# H-Bridge-HP.net
KiCad netlist of a schematic drawn in EAGLE
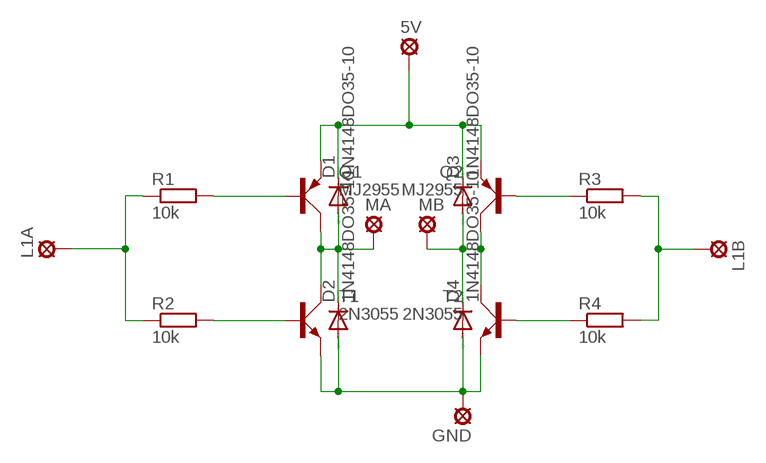
[diagram p0: schematic, sheet 1]

(export (version "E")
  (design (tool "Eeschema 10.0.6"))
  (components
    (comp (ref "5V")
      (value "LSP10")
      (footprint "eagle-import:LSP10")
      (libsource (lib "eagle-import") (part "LSP10"))
    )
    (comp (ref "D1")
      (value "1N4148DO35-10")
      (footprint "eagle-import:DO35-10")
      (libsource (lib "eagle-import") (part "1N4148DO35-10"))
    )
    (comp (ref "D2")
      (value "1N4148DO35-10")
      (footprint "eagle-import:DO35-10")
      (libsource (lib "eagle-import") (part "1N4148DO35-10"))
    )
    (comp (ref "D3")
      (value "1N4148DO35-10")
      (footprint "eagle-import:DO35-10")
      (libsource (lib "eagle-import") (part "1N4148DO35-10"))
    )
    (comp (ref "D4")
      (value "1N4148DO35-10")
      (footprint "eagle-import:DO35-10")
      (libsource (lib "eagle-import") (part "1N4148DO35-10"))
    )
    (comp (ref "GND")
      (value "LSP10")
      (footprint "eagle-import:LSP10")
      (libsource (lib "eagle-import") (part "LSP10"))
    )
    (comp (ref "L1A")
      (value "LSP10")
      (footprint "eagle-import:LSP10")
      (libsource (lib "eagle-import") (part "LSP10"))
    )
    (comp (ref "L1B")
      (value "LSP10")
      (footprint "eagle-import:LSP10")
      (libsource (lib "eagle-import") (part "LSP10"))
    )
    (comp (ref "MA")
      (value "LSP10")
      (footprint "eagle-import:LSP10")
      (libsource (lib "eagle-import") (part "LSP10"))
    )
    (comp (ref "MB")
      (value "LSP10")
      (footprint "eagle-import:LSP10")
      (libsource (lib "eagle-import") (part "LSP10"))
    )
    (comp (ref "Q1")
      (value "MJ2955")
      (footprint "eagle-import:TO3A")
      (libsource (lib "eagle-import") (part "MJ2955"))
    )
    (comp (ref "Q2")
      (value "MJ2955")
      (footprint "eagle-import:TO3A")
      (libsource (lib "eagle-import") (part "MJ2955"))
    )
    (comp (ref "R1")
      (value "10k")
      (footprint "eagle-import:0309_12")
      (libsource (lib "eagle-import") (part "R-EU_0309/12"))
    )
    (comp (ref "R2")
      (value "10k")
      (footprint "eagle-import:0309_12")
      (libsource (lib "eagle-import") (part "R-EU_0309/12"))
    )
    (comp (ref "R3")
      (value "10k")
      (footprint "eagle-import:0309_12")
      (libsource (lib "eagle-import") (part "R-EU_0309/12"))
    )
    (comp (ref "R4")
      (value "10k")
      (footprint "eagle-import:0309_12")
      (libsource (lib "eagle-import") (part "R-EU_0309/12"))
    )
    (comp (ref "T1")
      (value "2N3055")
      (footprint "eagle-import:TO3A")
      (libsource (lib "eagle-import") (part "2N3055"))
    )
    (comp (ref "T2")
      (value "2N3055")
      (footprint "eagle-import:TO3A")
      (libsource (lib "eagle-import") (part "2N3055"))
    )
  )
  (nets
    (net (code "1") (name "Net-(5V-PadMP)") (class "Default")
      (node (ref "5V") (pin "MP") (pinfunction "MP_MP") (pintype "passive"))
      (node (ref "D1") (pin "C") (pinfunction "C_C") (pintype "passive"))
      (node (ref "D3") (pin "C") (pinfunction "C_C") (pintype "passive"))
      (node (ref "Q1") (pin "E") (pinfunction "E_E") (pintype "passive"))
      (node (ref "Q2") (pin "E") (pinfunction "E_E") (pintype "passive"))
    )
    (net (code "2") (name "Net-(D1-PadA)") (class "Default")
      (node (ref "D1") (pin "A") (pinfunction "A_A") (pintype "passive"))
      (node (ref "D2") (pin "C") (pinfunction "C_C") (pintype "passive"))
      (node (ref "MA") (pin "MP") (pinfunction "MP_MP") (pintype "passive"))
      (node (ref "Q1") (pin "C") (pinfunction "C_C") (pintype "passive"))
      (node (ref "Q1") (pin "C1") (pinfunction "C_C1") (pintype "passive"))
      (node (ref "T1") (pin "C") (pinfunction "C_C") (pintype "passive"))
      (node (ref "T1") (pin "C1") (pinfunction "C_C1") (pintype "passive"))
    )
    (net (code "3") (name "Net-(D2-PadA)") (class "Default")
      (node (ref "D2") (pin "A") (pinfunction "A_A") (pintype "passive"))
      (node (ref "D4") (pin "A") (pinfunction "A_A") (pintype "passive"))
      (node (ref "GND") (pin "MP") (pinfunction "MP_MP") (pintype "passive"))
      (node (ref "T1") (pin "E") (pinfunction "E_E") (pintype "passive"))
      (node (ref "T2") (pin "E") (pinfunction "E_E") (pintype "passive"))
    )
    (net (code "4") (name "Net-(D3-PadA)") (class "Default")
      (node (ref "D3") (pin "A") (pinfunction "A_A") (pintype "passive"))
      (node (ref "D4") (pin "C") (pinfunction "C_C") (pintype "passive"))
      (node (ref "MB") (pin "MP") (pinfunction "MP_MP") (pintype "passive"))
      (node (ref "Q2") (pin "C") (pinfunction "C_C") (pintype "passive"))
      (node (ref "Q2") (pin "C1") (pinfunction "C_C1") (pintype "passive"))
      (node (ref "T2") (pin "C") (pinfunction "C_C") (pintype "passive"))
      (node (ref "T2") (pin "C1") (pinfunction "C_C1") (pintype "passive"))
    )
    (net (code "5") (name "Net-(L1A-PadMP)") (class "Default")
      (node (ref "L1A") (pin "MP") (pinfunction "MP_MP") (pintype "passive"))
      (node (ref "R1") (pin "1") (pinfunction "1_1") (pintype "passive"))
      (node (ref "R2") (pin "1") (pinfunction "1_1") (pintype "passive"))
    )
    (net (code "6") (name "Net-(L1B-PadMP)") (class "Default")
      (node (ref "L1B") (pin "MP") (pinfunction "MP_MP") (pintype "passive"))
      (node (ref "R3") (pin "2") (pinfunction "2_2") (pintype "passive"))
      (node (ref "R4") (pin "2") (pinfunction "2_2") (pintype "passive"))
    )
    (net (code "7") (name "Net-(Q1-PadB)") (class "Default")
      (node (ref "Q1") (pin "B") (pinfunction "B_B") (pintype "passive"))
      (node (ref "R1") (pin "2") (pinfunction "2_2") (pintype "passive"))
    )
    (net (code "8") (name "Net-(Q2-PadB)") (class "Default")
      (node (ref "Q2") (pin "B") (pinfunction "B_B") (pintype "passive"))
      (node (ref "R3") (pin "1") (pinfunction "1_1") (pintype "passive"))
    )
    (net (code "9") (name "Net-(R2-Pad2)") (class "Default")
      (node (ref "R2") (pin "2") (pinfunction "2_2") (pintype "passive"))
      (node (ref "T1") (pin "B") (pinfunction "B_B") (pintype "passive"))
    )
    (net (code "10") (name "Net-(R4-Pad1)") (class "Default")
      (node (ref "R4") (pin "1") (pinfunction "1_1") (pintype "passive"))
      (node (ref "T2") (pin "B") (pinfunction "B_B") (pintype "passive"))
    )
  )
)
